# untitled.net
KiCad netlist of a schematic drawn in EAGLE
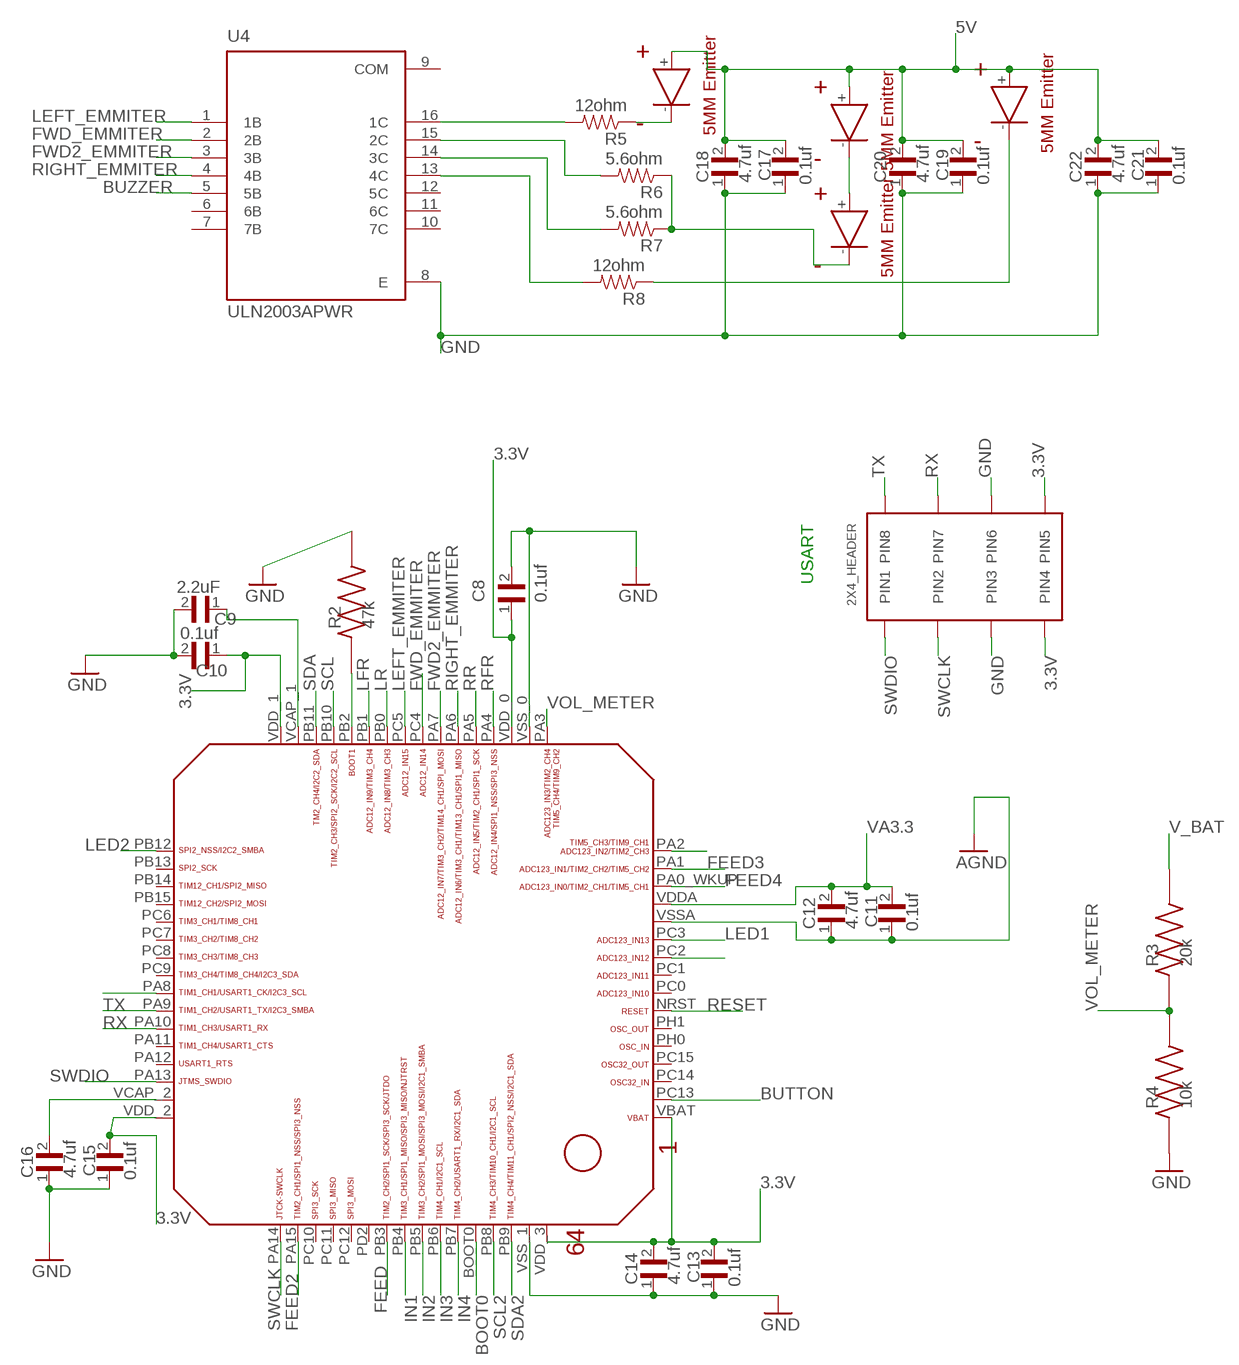
[diagram p0: schematic, sheet 1, part 1 of 2]
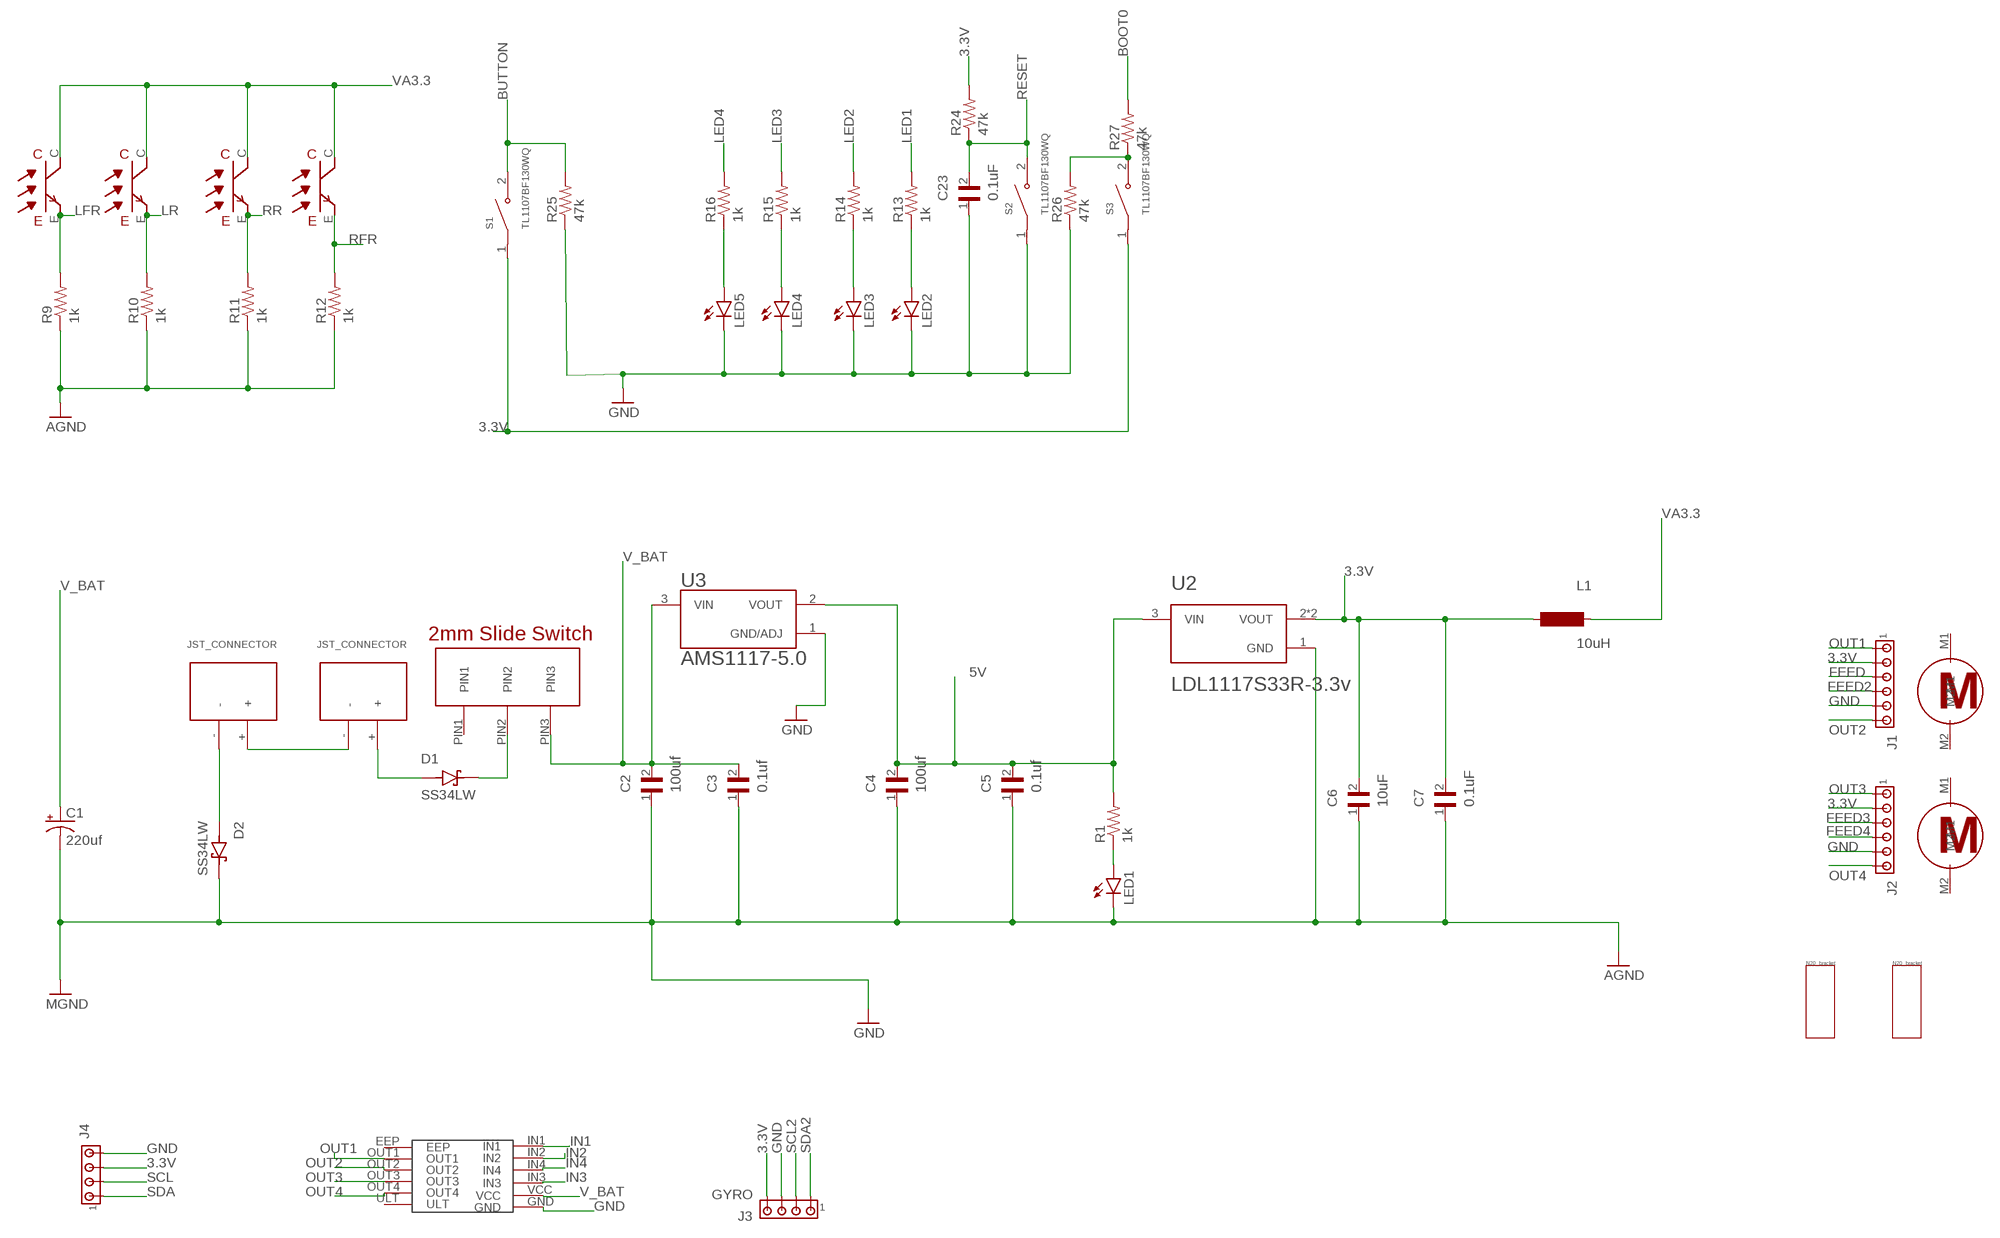
[diagram p1: schematic, sheet 1, part 2 of 2]

(export (version "E")
  (design (tool "Eeschema 10.0.6"))
  (components
    (comp (ref "C1")
      (value "220uf")
      (footprint "eagle-import:EIA3216")
      (libsource (lib "eagle-import") (part "CAP_POL1206"))
    )
    (comp (ref "C2")
      (value "100uf")
      (footprint "eagle-import:CAPC0603X35N")
      (fields (field (name "MF") "Murata") (field (name "MP") "GRM033R60J105MEA2D"))
      (libsource (lib "eagle-import") (part "GRM033R60J105MEA2D"))
    )
    (comp (ref "C3")
      (value "0.1uf")
      (footprint "eagle-import:CAPC0603X35N")
      (fields (field (name "MF") "Murata") (field (name "MP") "GRM033R60J105MEA2D"))
      (libsource (lib "eagle-import") (part "GRM033R60J105MEA2D"))
    )
    (comp (ref "C4")
      (value "100uf")
      (footprint "eagle-import:CAPC0603X35N")
      (fields (field (name "MF") "Murata") (field (name "MP") "GRM033R60J105MEA2D"))
      (libsource (lib "eagle-import") (part "GRM033R60J105MEA2D"))
    )
    (comp (ref "C5")
      (value "0.1uf")
      (footprint "eagle-import:CAPC0603X35N")
      (fields (field (name "MF") "Murata") (field (name "MP") "GRM033R60J105MEA2D"))
      (libsource (lib "eagle-import") (part "GRM033R60J105MEA2D"))
    )
    (comp (ref "C6")
      (value "10uF")
      (footprint "eagle-import:CAPC0603X35N")
      (fields (field (name "MF") "Murata") (field (name "MP") "GRM033R60J105MEA2D"))
      (libsource (lib "eagle-import") (part "GRM033R60J105MEA2D"))
    )
    (comp (ref "C7")
      (value "0.1uF")
      (footprint "eagle-import:CAPC0603X35N")
      (fields (field (name "MF") "Murata") (field (name "MP") "GRM033R60J105MEA2D"))
      (libsource (lib "eagle-import") (part "GRM033R60J105MEA2D"))
    )
    (comp (ref "C8")
      (value "0.1uf")
      (footprint "eagle-import:CAPC0603X35N")
      (fields (field (name "MF") "Murata") (field (name "MP") "GRM033R60J105MEA2D"))
      (libsource (lib "eagle-import") (part "GRM033R60J105MEA2D"))
    )
    (comp (ref "C9")
      (value "2.2uF")
      (footprint "eagle-import:CAPC0603X35N")
      (fields (field (name "MF") "Murata") (field (name "MP") "GRM033R60J105MEA2D"))
      (libsource (lib "eagle-import") (part "GRM033R60J105MEA2D"))
    )
    (comp (ref "C10")
      (value "0.1uf")
      (footprint "eagle-import:CAPC0603X35N")
      (fields (field (name "MF") "Murata") (field (name "MP") "GRM033R60J105MEA2D"))
      (libsource (lib "eagle-import") (part "GRM033R60J105MEA2D"))
    )
    (comp (ref "C11")
      (value "0.1uf")
      (footprint "eagle-import:CAPC0603X35N")
      (fields (field (name "MF") "Murata") (field (name "MP") "GRM033R60J105MEA2D"))
      (libsource (lib "eagle-import") (part "GRM033R60J105MEA2D"))
    )
    (comp (ref "C12")
      (value "4.7uf")
      (footprint "eagle-import:CAPC0603X35N")
      (fields (field (name "MF") "Murata") (field (name "MP") "GRM033R60J105MEA2D"))
      (libsource (lib "eagle-import") (part "GRM033R60J105MEA2D"))
    )
    (comp (ref "C13")
      (value "0.1uf")
      (footprint "eagle-import:CAPC0603X35N")
      (fields (field (name "MF") "Murata") (field (name "MP") "GRM033R60J105MEA2D"))
      (libsource (lib "eagle-import") (part "GRM033R60J105MEA2D"))
    )
    (comp (ref "C14")
      (value "4.7uf")
      (footprint "eagle-import:CAPC0603X35N")
      (fields (field (name "MF") "Murata") (field (name "MP") "GRM033R60J105MEA2D"))
      (libsource (lib "eagle-import") (part "GRM033R60J105MEA2D"))
    )
    (comp (ref "C15")
      (value "0.1uf")
      (footprint "eagle-import:CAPC0603X35N")
      (fields (field (name "MF") "Murata") (field (name "MP") "GRM033R60J105MEA2D"))
      (libsource (lib "eagle-import") (part "GRM033R60J105MEA2D"))
    )
    (comp (ref "C16")
      (value "4.7uf")
      (footprint "eagle-import:CAPC0603X35N")
      (fields (field (name "MF") "Murata") (field (name "MP") "GRM033R60J105MEA2D"))
      (libsource (lib "eagle-import") (part "GRM033R60J105MEA2D"))
    )
    (comp (ref "C17")
      (value "0.1uf")
      (footprint "eagle-import:CAPC0603X35N")
      (fields (field (name "MF") "Murata") (field (name "MP") "GRM033R60J105MEA2D"))
      (libsource (lib "eagle-import") (part "GRM033R60J105MEA2D"))
    )
    (comp (ref "C18")
      (value "4.7uf")
      (footprint "eagle-import:CAPC0603X35N")
      (fields (field (name "MF") "Murata") (field (name "MP") "GRM033R60J105MEA2D"))
      (libsource (lib "eagle-import") (part "GRM033R60J105MEA2D"))
    )
    (comp (ref "C19")
      (value "0.1uf")
      (footprint "eagle-import:CAPC0603X35N")
      (fields (field (name "MF") "Murata") (field (name "MP") "GRM033R60J105MEA2D"))
      (libsource (lib "eagle-import") (part "GRM033R60J105MEA2D"))
    )
    (comp (ref "C20")
      (value "4.7uf")
      (footprint "eagle-import:CAPC0603X35N")
      (fields (field (name "MF") "Murata") (field (name "MP") "GRM033R60J105MEA2D"))
      (libsource (lib "eagle-import") (part "GRM033R60J105MEA2D"))
    )
    (comp (ref "C21")
      (value "0.1uf")
      (footprint "eagle-import:CAPC0603X35N")
      (fields (field (name "MF") "Murata") (field (name "MP") "GRM033R60J105MEA2D"))
      (libsource (lib "eagle-import") (part "GRM033R60J105MEA2D"))
    )
    (comp (ref "C22")
      (value "4.7uf")
      (footprint "eagle-import:CAPC0603X35N")
      (fields (field (name "MF") "Murata") (field (name "MP") "GRM033R60J105MEA2D"))
      (libsource (lib "eagle-import") (part "GRM033R60J105MEA2D"))
    )
    (comp (ref "C23")
      (value "0.1uF")
      (footprint "eagle-import:CAPC0603X35N")
      (fields (field (name "MF") "Murata") (field (name "MP") "GRM033R60J105MEA2D"))
      (libsource (lib "eagle-import") (part "GRM033R60J105MEA2D"))
    )
    (comp (ref "D1")
      (value "SS34LW")
      (footprint "eagle-import:SODFL3718X102N")
      (fields (field (name "MF") "Taiwan Semiconductor"))
      (libsource (lib "eagle-import") (part "SS34LW"))
    )
    (comp (ref "D2")
      (value "SS34LW")
      (footprint "eagle-import:SODFL3718X102N")
      (fields (field (name "MF") "Taiwan Semiconductor"))
      (libsource (lib "eagle-import") (part "SS34LW"))
    )
    (comp (ref "EMMI1")
      (value "EMITTER")
      (footprint "eagle-import:EMITTER")
      (libsource (lib "eagle-import") (part "EMITTER"))
    )
    (comp (ref "J1")
      (value "MTA06-100")
      (footprint "eagle-import:10X06MTA")
      (libsource (lib "eagle-import") (part "MTA06-100"))
    )
    (comp (ref "J2")
      (value "MTA06-100")
      (footprint "eagle-import:10X06MTA")
      (libsource (lib "eagle-import") (part "MTA06-100"))
    )
    (comp (ref "J3")
      (value "GYRO")
      (footprint "eagle-import:10X04MTA")
      (libsource (lib "eagle-import") (part "MTA04-100"))
    )
    (comp (ref "J4")
      (value "MTA04-100")
      (footprint "eagle-import:10X04MTA")
      (libsource (lib "eagle-import") (part "MTA04-100"))
    )
    (comp (ref "L1")
      (value "10uH")
      (footprint "eagle-import:MS42")
      (libsource (lib "eagle-import") (part "MS42"))
    )
    (comp (ref "LED1")
      (value "LEDCHIPLED_0805")
      (footprint "eagle-import:CHIPLED_0805")
      (libsource (lib "eagle-import") (part "LEDCHIPLED_0805"))
    )
    (comp (ref "LED2")
      (value "LEDCHIPLED_0805")
      (footprint "eagle-import:CHIPLED_0805")
      (libsource (lib "eagle-import") (part "LEDCHIPLED_0805"))
    )
    (comp (ref "LED3")
      (value "LEDCHIPLED_0805")
      (footprint "eagle-import:CHIPLED_0805")
      (libsource (lib "eagle-import") (part "LEDCHIPLED_0805"))
    )
    (comp (ref "LED4")
      (value "LEDCHIPLED_0805")
      (footprint "eagle-import:CHIPLED_0805")
      (libsource (lib "eagle-import") (part "LEDCHIPLED_0805"))
    )
    (comp (ref "LED5")
      (value "LEDCHIPLED_0805")
      (footprint "eagle-import:CHIPLED_0805")
      (libsource (lib "eagle-import") (part "LEDCHIPLED_0805"))
    )
    (comp (ref "R1")
      (value "1k")
      (footprint "eagle-import:0603-RES")
      (libsource (lib "eagle-import") (part "RESISTOR0603-RES"))
    )
    (comp (ref "R2")
      (value "47k")
      (footprint "eagle-import:RES_ERJU01F3570C")
      (fields (field (name "MF") "Panasonic") (field (name "MP") "ERJ-U01F3570C"))
      (libsource (lib "eagle-import") (part "ERJU01F3570C"))
    )
    (comp (ref "R3")
      (value "20k")
      (footprint "eagle-import:RES_ERJU01F3570C")
      (fields (field (name "MF") "Panasonic") (field (name "MP") "ERJ-U01F3570C"))
      (libsource (lib "eagle-import") (part "ERJU01F3570C"))
    )
    (comp (ref "R4")
      (value "10k")
      (footprint "eagle-import:RES_ERJU01F3570C")
      (fields (field (name "MF") "Panasonic") (field (name "MP") "ERJ-U01F3570C"))
      (libsource (lib "eagle-import") (part "ERJU01F3570C"))
    )
    (comp (ref "R5")
      (value "12ohm")
      (footprint "eagle-import:0603-RES")
      (libsource (lib "eagle-import") (part "RESISTOR0603-RES"))
    )
    (comp (ref "R6")
      (value "5.6ohm")
      (footprint "eagle-import:0603-RES")
      (libsource (lib "eagle-import") (part "RESISTOR0603-RES"))
    )
    (comp (ref "R7")
      (value "5.6ohm")
      (footprint "eagle-import:0603-RES")
      (libsource (lib "eagle-import") (part "RESISTOR0603-RES"))
    )
    (comp (ref "R8")
      (value "12ohm")
      (footprint "eagle-import:0603-RES")
      (libsource (lib "eagle-import") (part "RESISTOR0603-RES"))
    )
    (comp (ref "R9")
      (value "1k")
      (footprint "eagle-import:0603-RES")
      (libsource (lib "eagle-import") (part "RESISTOR0603-RES"))
    )
    (comp (ref "R10")
      (value "1k")
      (footprint "eagle-import:0603-RES")
      (libsource (lib "eagle-import") (part "RESISTOR0603-RES"))
    )
    (comp (ref "R11")
      (value "1k")
      (footprint "eagle-import:0603-RES")
      (libsource (lib "eagle-import") (part "RESISTOR0603-RES"))
    )
    (comp (ref "R12")
      (value "1k")
      (footprint "eagle-import:0603-RES")
      (libsource (lib "eagle-import") (part "RESISTOR0603-RES"))
    )
    (comp (ref "R13")
      (value "1k")
      (footprint "eagle-import:0603-RES")
      (libsource (lib "eagle-import") (part "RESISTOR0603-RES"))
    )
    (comp (ref "R14")
      (value "1k")
      (footprint "eagle-import:0603-RES")
      (libsource (lib "eagle-import") (part "RESISTOR0603-RES"))
    )
    (comp (ref "R15")
      (value "1k")
      (footprint "eagle-import:0603-RES")
      (libsource (lib "eagle-import") (part "RESISTOR0603-RES"))
    )
    (comp (ref "R16")
      (value "1k")
      (footprint "eagle-import:0603-RES")
      (libsource (lib "eagle-import") (part "RESISTOR0603-RES"))
    )
    (comp (ref "R24")
      (value "47k")
      (footprint "eagle-import:0603-RES")
      (libsource (lib "eagle-import") (part "RESISTOR0603-RES"))
    )
    (comp (ref "R25")
      (value "47k")
      (footprint "eagle-import:0603-RES")
      (libsource (lib "eagle-import") (part "RESISTOR0603-RES"))
    )
    (comp (ref "R26")
      (value "47k")
      (footprint "eagle-import:0603-RES")
      (libsource (lib "eagle-import") (part "RESISTOR0603-RES"))
    )
    (comp (ref "R27")
      (value "47k")
      (footprint "eagle-import:0603-RES")
      (libsource (lib "eagle-import") (part "RESISTOR0603-RES"))
    )
    (comp (ref "S1")
      (value "TL1107BF130WQ")
      (footprint "eagle-import:SW_TL1107BF130WQ")
      (fields (field (name "MF") "E-Switch"))
      (libsource (lib "eagle-import") (part "TL1107BF130WQ"))
    )
    (comp (ref "S2")
      (value "TL1107BF130WQ")
      (footprint "eagle-import:SW_TL1107BF130WQ")
      (fields (field (name "MF") "E-Switch"))
      (libsource (lib "eagle-import") (part "TL1107BF130WQ"))
    )
    (comp (ref "S3")
      (value "TL1107BF130WQ")
      (footprint "eagle-import:SW_TL1107BF130WQ")
      (fields (field (name "MF") "E-Switch"))
      (libsource (lib "eagle-import") (part "TL1107BF130WQ"))
    )
    (comp (ref "STM32F405RGT6")
      (value "STM32F405/415_LQFP64")
      (footprint "eagle-import:STM32F405_415_LQFP64")
      (libsource (lib "eagle-import") (part "STM32F405/415_LQFP64"))
    )
    (comp (ref "U$1")
      (value "N20_BRACKET")
      (footprint "eagle-import:BRACKER")
      (libsource (lib "eagle-import") (part "N20_BRACKET"))
    )
    (comp (ref "U$2")
      (value "MOTOR_N20")
      (footprint "eagle-import:MOTOR_N20")
      (libsource (lib "eagle-import") (part "MOTOR_N20"))
    )
    (comp (ref "U$3")
      (value "MOTOR_N20")
      (footprint "eagle-import:MOTOR_N20")
      (libsource (lib "eagle-import") (part "MOTOR_N20"))
    )
    (comp (ref "U$4")
      (value "N20_BRACKET")
      (footprint "eagle-import:BRACKER")
      (libsource (lib "eagle-import") (part "N20_BRACKET"))
    )
    (comp (ref "U$5")
      (value "JST_CONNECTOR_FEMALE")
      (footprint "eagle-import:JST_CONNECTOR_FEMALE")
      (libsource (lib "eagle-import") (part "JST_CONNECTOR_FEMALE"))
    )
    (comp (ref "U$6")
      (value "JST_CONNECTOR_FEMALE")
      (footprint "eagle-import:JST_CONNECTOR_FEMALE")
      (libsource (lib "eagle-import") (part "JST_CONNECTOR_FEMALE"))
    )
    (comp (ref "U$8")
      (value "2MMS_SLIDE_SWITCH")
      (footprint "eagle-import:2MMS_SLIDE_SWITCH")
      (libsource (lib "eagle-import") (part "2MMS_SLIDE_SWITCH"))
    )
    (comp (ref "U$10")
      (value "2X3_HEADER")
      (footprint "eagle-import:2X3_HEADER")
      (libsource (lib "eagle-import") (part "2X3_HEADER"))
    )
    (comp (ref "U$11")
      (value "DRV8833")
      (footprint "eagle-import:DRV8833")
      (libsource (lib "eagle-import") (part "DRV8833"))
    )
    (comp (ref "U$12")
      (value "RECEIVER")
      (footprint "eagle-import:RECEIVER")
      (libsource (lib "eagle-import") (part "RECEIVER"))
    )
    (comp (ref "U$13")
      (value "EMITTER")
      (footprint "eagle-import:EMITTER")
      (libsource (lib "eagle-import") (part "EMITTER"))
    )
    (comp (ref "U$14")
      (value "EMITTER")
      (footprint "eagle-import:EMITTER")
      (libsource (lib "eagle-import") (part "EMITTER"))
    )
    (comp (ref "U$15")
      (value "EMITTER")
      (footprint "eagle-import:EMITTER")
      (libsource (lib "eagle-import") (part "EMITTER"))
    )
    (comp (ref "U$16")
      (value "RECEIVER")
      (footprint "eagle-import:RECEIVER")
      (libsource (lib "eagle-import") (part "RECEIVER"))
    )
    (comp (ref "U$17")
      (value "RECEIVER")
      (footprint "eagle-import:RECEIVER")
      (libsource (lib "eagle-import") (part "RECEIVER"))
    )
    (comp (ref "U$18")
      (value "RECEIVER")
      (footprint "eagle-import:RECEIVER")
      (libsource (lib "eagle-import") (part "RECEIVER"))
    )
    (comp (ref "U2")
      (value "LDL1117S33R-3.3v")
      (footprint "eagle-import:SOT230P700X180-4N")
      (fields (field (name "MF") "STMicroelectronics") (field (name "MP") "LDL1117S33R"))
      (libsource (lib "eagle-import") (part "LDL1117S33R"))
    )
    (comp (ref "U3")
      (value "AMS1117-5.0")
      (footprint "eagle-import:SOT229P700X180-4N")
      (fields (field (name "MF") "Advanced Monolithic Systems"))
      (libsource (lib "eagle-import") (part "AMS1117-5.0"))
    )
    (comp (ref "U4")
      (value "ULN2003APWR")
      (footprint "eagle-import:SOP65P640X120-16N")
      (fields (field (name "MF") "Texas Instruments"))
      (libsource (lib "eagle-import") (part "ULN2003APWR"))
    )
  )
  (nets
    (net (code "1") (name "/3.3V") (class "Default")
      (node (ref "C10") (pin "1") (pinfunction "1_1") (pintype "passive"))
      (node (ref "C13") (pin "2") (pinfunction "2_2") (pintype "passive"))
      (node (ref "C14") (pin "2") (pinfunction "2_2") (pintype "passive"))
      (node (ref "C15") (pin "2") (pinfunction "2_2") (pintype "passive"))
      (node (ref "C6") (pin "2") (pinfunction "2_2") (pintype "passive"))
      (node (ref "C7") (pin "2") (pinfunction "2_2") (pintype "passive"))
      (node (ref "C8") (pin "1") (pinfunction "1_1") (pintype "passive"))
      (node (ref "J1") (pin "2") (pinfunction "2_2") (pintype "passive"))
      (node (ref "J2") (pin "2") (pinfunction "2_2") (pintype "passive"))
      (node (ref "J3") (pin "4") (pinfunction "4_4") (pintype "passive"))
      (node (ref "J4") (pin "3") (pinfunction "3_3") (pintype "passive"))
      (node (ref "L1") (pin "1") (pinfunction "1_1") (pintype "passive"))
      (node (ref "R24") (pin "2") (pinfunction "2_2") (pintype "passive"))
      (node (ref "S1") (pin "1") (pinfunction "1_1") (pintype "passive"))
      (node (ref "S3") (pin "1") (pinfunction "1_1") (pintype "passive"))
      (node (ref "STM32F405RGT6") (pin "VBAT") (pinfunction "VBAT_VBAT") (pintype "bidirectional"))
      (node (ref "STM32F405RGT6") (pin "VDD_0") (pinfunction "VDD_0_VDD_0") (pintype "bidirectional"))
      (node (ref "STM32F405RGT6") (pin "VDD_1") (pinfunction "VDD_1_VDD_1") (pintype "bidirectional"))
      (node (ref "STM32F405RGT6") (pin "VDD_2") (pinfunction "VDD_2_VDD_2") (pintype "bidirectional"))
      (node (ref "STM32F405RGT6") (pin "VDD_3") (pinfunction "VDD_3_VDD_3") (pintype "bidirectional"))
      (node (ref "U$10") (pin "PIN4") (pinfunction "PIN4_PIN4") (pintype "bidirectional"))
      (node (ref "U$10") (pin "PIN5") (pinfunction "PIN5_PIN5") (pintype "bidirectional"))
      (node (ref "U2") (pin "2") (pinfunction "VOUT_2") (pintype "output"))
      (node (ref "U2") (pin "4") (pinfunction "VOUT_4") (pintype "output"))
    )
    (net (code "2") (name "/5V") (class "Default")
      (node (ref "C17") (pin "2") (pinfunction "2_2") (pintype "passive"))
      (node (ref "C18") (pin "2") (pinfunction "2_2") (pintype "passive"))
      (node (ref "C19") (pin "2") (pinfunction "2_2") (pintype "passive"))
      (node (ref "C20") (pin "2") (pinfunction "2_2") (pintype "passive"))
      (node (ref "C21") (pin "2") (pinfunction "2_2") (pintype "passive"))
      (node (ref "C22") (pin "2") (pinfunction "2_2") (pintype "passive"))
      (node (ref "C4") (pin "2") (pinfunction "2_2") (pintype "passive"))
      (node (ref "C5") (pin "2") (pinfunction "2_2") (pintype "passive"))
      (node (ref "EMMI1") (pin "+") (pinfunction "+_+") (pintype "bidirectional"))
      (node (ref "R1") (pin "2") (pinfunction "2_2") (pintype "passive"))
      (node (ref "U$13") (pin "+") (pinfunction "+_+") (pintype "bidirectional"))
      (node (ref "U$15") (pin "+") (pinfunction "+_+") (pintype "bidirectional"))
      (node (ref "U2") (pin "3") (pinfunction "VIN_3") (pintype "input"))
      (node (ref "U3") (pin "2") (pinfunction "VOUT_2") (pintype "output"))
    )
    (net (code "3") (name "/BOOT0") (class "Default")
      (node (ref "R27") (pin "2") (pinfunction "2_2") (pintype "passive"))
      (node (ref "STM32F405RGT6") (pin "BOOT0") (pinfunction "BOOT0_BOOT0") (pintype "bidirectional"))
    )
    (net (code "4") (name "/BUTTON") (class "Default")
      (node (ref "R25") (pin "2") (pinfunction "2_2") (pintype "passive"))
      (node (ref "S1") (pin "2") (pinfunction "2_2") (pintype "passive"))
      (node (ref "STM32F405RGT6") (pin "PC13") (pinfunction "PC13_PC13") (pintype "bidirectional"))
    )
    (net (code "5") (name "/BUZZER") (class "Default")
      (node (ref "U4") (pin "5") (pinfunction "5B_5") (pintype "input"))
    )
    (net (code "6") (name "/COM") (class "Default")
      (node (ref "U4") (pin "9") (pinfunction "COM_9") (pintype "power_in"))
    )
    (net (code "7") (name "/FEED") (class "Default")
      (node (ref "J1") (pin "3") (pinfunction "3_3") (pintype "passive"))
      (node (ref "STM32F405RGT6") (pin "PB3") (pinfunction "PB3_PB3") (pintype "bidirectional"))
    )
    (net (code "8") (name "/FEED2") (class "Default")
      (node (ref "J1") (pin "4") (pinfunction "4_4") (pintype "passive"))
      (node (ref "STM32F405RGT6") (pin "PA15") (pinfunction "PA15_PA15") (pintype "bidirectional"))
    )
    (net (code "9") (name "/FEED3") (class "Default")
      (node (ref "J2") (pin "3") (pinfunction "3_3") (pintype "passive"))
      (node (ref "STM32F405RGT6") (pin "PA1") (pinfunction "PA1_PA1") (pintype "bidirectional"))
    )
    (net (code "10") (name "/FEED4") (class "Default")
      (node (ref "J2") (pin "4") (pinfunction "4_4") (pintype "passive"))
      (node (ref "STM32F405RGT6") (pin "PA0_WKUP") (pinfunction "PA0_AKUP_PA0_WKUP") (pintype "bidirectional"))
    )
    (net (code "11") (name "/FWD2_EMMITER") (class "Default")
      (node (ref "STM32F405RGT6") (pin "PA7") (pinfunction "PA7_PA7") (pintype "bidirectional"))
      (node (ref "U4") (pin "3") (pinfunction "3B_3") (pintype "input"))
    )
    (net (code "12") (name "/FWD_EMMITER") (class "Default")
      (node (ref "STM32F405RGT6") (pin "PC4") (pinfunction "PC4_PC4") (pintype "bidirectional"))
      (node (ref "U4") (pin "2") (pinfunction "2B_2") (pintype "input"))
    )
    (net (code "13") (name "/IN1") (class "Default")
      (node (ref "STM32F405RGT6") (pin "PB4") (pinfunction "PB4_PB4") (pintype "bidirectional"))
      (node (ref "U$11") (pin "IN1") (pinfunction "IN1_IN1") (pintype "bidirectional"))
    )
    (net (code "14") (name "/IN2") (class "Default")
      (node (ref "STM32F405RGT6") (pin "PB5") (pinfunction "PB5_PB5") (pintype "bidirectional"))
      (node (ref "U$11") (pin "IN2") (pinfunction "IN2_IN2") (pintype "bidirectional"))
    )
    (net (code "15") (name "/IN3") (class "Default")
      (node (ref "STM32F405RGT6") (pin "PB6") (pinfunction "PB6_PB6") (pintype "bidirectional"))
      (node (ref "U$11") (pin "IN3") (pinfunction "IN3_IN3") (pintype "bidirectional"))
    )
    (net (code "16") (name "/IN4") (class "Default")
      (node (ref "STM32F405RGT6") (pin "PB7") (pinfunction "PB7_PB7") (pintype "bidirectional"))
      (node (ref "U$11") (pin "IN4") (pinfunction "IN4_IN4") (pintype "bidirectional"))
    )
    (net (code "17") (name "/LED1") (class "Default")
      (node (ref "R13") (pin "2") (pinfunction "2_2") (pintype "passive"))
      (node (ref "STM32F405RGT6") (pin "PC3") (pinfunction "PC3_PC3") (pintype "bidirectional"))
    )
    (net (code "18") (name "/LED2") (class "Default")
      (node (ref "R14") (pin "2") (pinfunction "2_2") (pintype "passive"))
      (node (ref "STM32F405RGT6") (pin "PB12") (pinfunction "PB12_PB12") (pintype "bidirectional"))
    )
    (net (code "19") (name "/LED3") (class "Default")
      (node (ref "R15") (pin "2") (pinfunction "2_2") (pintype "passive"))
      (node (ref "STM32F405RGT6") (pin "PC2") (pinfunction "PC2_PC2") (pintype "bidirectional"))
    )
    (net (code "20") (name "/LED4") (class "Default")
      (node (ref "R16") (pin "2") (pinfunction "2_2") (pintype "passive"))
      (node (ref "STM32F405RGT6") (pin "PA8") (pinfunction "PA8_PA8") (pintype "bidirectional"))
    )
    (net (code "21") (name "/LEFT_EMMITER") (class "Default")
      (node (ref "STM32F405RGT6") (pin "PC5") (pinfunction "PC5_PC5") (pintype "bidirectional"))
      (node (ref "U4") (pin "1") (pinfunction "1B_1") (pintype "input"))
    )
    (net (code "22") (name "/LFR") (class "Default")
      (node (ref "R9") (pin "2") (pinfunction "2_2") (pintype "passive"))
      (node (ref "STM32F405RGT6") (pin "PB1") (pinfunction "PB1_PB1") (pintype "bidirectional"))
      (node (ref "U$18") (pin "E") (pinfunction "E_E") (pintype "bidirectional"))
    )
    (net (code "23") (name "/LR") (class "Default")
      (node (ref "R10") (pin "2") (pinfunction "2_2") (pintype "passive"))
      (node (ref "STM32F405RGT6") (pin "PB0") (pinfunction "PB0_PB0") (pintype "bidirectional"))
      (node (ref "U$17") (pin "E") (pinfunction "E_E") (pintype "bidirectional"))
    )
    (net (code "24") (name "/OUT1") (class "Default")
      (node (ref "J1") (pin "1") (pinfunction "1_1") (pintype "passive"))
      (node (ref "U$11") (pin "OUT1") (pinfunction "OUT1_OUT1") (pintype "bidirectional"))
    )
    (net (code "25") (name "/OUT2") (class "Default")
      (node (ref "J1") (pin "6") (pinfunction "6_6") (pintype "passive"))
      (node (ref "U$11") (pin "OUT2") (pinfunction "OUT2_OUT2") (pintype "bidirectional"))
    )
    (net (code "26") (name "/OUT3") (class "Default")
      (node (ref "J2") (pin "1") (pinfunction "1_1") (pintype "passive"))
      (node (ref "U$11") (pin "OUT3") (pinfunction "OUT3_OUT3") (pintype "bidirectional"))
    )
    (net (code "27") (name "/OUT4") (class "Default")
      (node (ref "J2") (pin "6") (pinfunction "6_6") (pintype "passive"))
      (node (ref "U$11") (pin "OUT4") (pinfunction "OUT4_OUT4") (pintype "bidirectional"))
    )
    (net (code "28") (name "/RESET") (class "Default")
      (node (ref "C23") (pin "2") (pinfunction "2_2") (pintype "passive"))
      (node (ref "R24") (pin "1") (pinfunction "1_1") (pintype "passive"))
      (node (ref "S2") (pin "2") (pinfunction "2_2") (pintype "passive"))
      (node (ref "STM32F405RGT6") (pin "NRST") (pinfunction "NRST_NRST") (pintype "bidirectional"))
    )
    (net (code "29") (name "/RFR") (class "Default")
      (node (ref "R12") (pin "2") (pinfunction "2_2") (pintype "passive"))
      (node (ref "STM32F405RGT6") (pin "PA4") (pinfunction "PA4_PA4") (pintype "bidirectional"))
      (node (ref "U$12") (pin "E") (pinfunction "E_E") (pintype "bidirectional"))
    )
    (net (code "30") (name "/RIGHT_EMMITER") (class "Default")
      (node (ref "STM32F405RGT6") (pin "PA6") (pinfunction "PA6_PA6") (pintype "bidirectional"))
      (node (ref "U4") (pin "4") (pinfunction "4B_4") (pintype "input"))
    )
    (net (code "31") (name "/RR") (class "Default")
      (node (ref "R11") (pin "2") (pinfunction "2_2") (pintype "passive"))
      (node (ref "STM32F405RGT6") (pin "PA5") (pinfunction "PA5_PA5") (pintype "bidirectional"))
      (node (ref "U$16") (pin "E") (pinfunction "E_E") (pintype "bidirectional"))
    )
    (net (code "32") (name "/RX") (class "Default")
      (node (ref "STM32F405RGT6") (pin "PA10") (pinfunction "PA10_PA10") (pintype "bidirectional"))
      (node (ref "U$10") (pin "PIN7") (pinfunction "PIN7_PIN7") (pintype "bidirectional"))
    )
    (net (code "33") (name "/SCL") (class "Default")
      (node (ref "J4") (pin "2") (pinfunction "2_2") (pintype "passive"))
      (node (ref "STM32F405RGT6") (pin "PB10") (pinfunction "PB10_PB10") (pintype "bidirectional"))
    )
    (net (code "34") (name "/SCL2") (class "Default")
      (node (ref "J3") (pin "2") (pinfunction "2_2") (pintype "passive"))
      (node (ref "STM32F405RGT6") (pin "PB8") (pinfunction "PB8_PB8") (pintype "bidirectional"))
    )
    (net (code "35") (name "/SDA") (class "Default")
      (node (ref "J4") (pin "1") (pinfunction "1_1") (pintype "passive"))
      (node (ref "STM32F405RGT6") (pin "PB11") (pinfunction "PB11_PB11") (pintype "bidirectional"))
    )
    (net (code "36") (name "/SDA2") (class "Default")
      (node (ref "J3") (pin "1") (pinfunction "1_1") (pintype "passive"))
      (node (ref "STM32F405RGT6") (pin "PB9") (pinfunction "PB9_PB9") (pintype "bidirectional"))
    )
    (net (code "37") (name "/SWCLK") (class "Default")
      (node (ref "STM32F405RGT6") (pin "PA14") (pinfunction "PA14_PA14") (pintype "bidirectional"))
      (node (ref "U$10") (pin "PIN2") (pinfunction "PIN2_PIN2") (pintype "bidirectional"))
    )
    (net (code "38") (name "/SWDIO") (class "Default")
      (node (ref "STM32F405RGT6") (pin "PA13") (pinfunction "PA13_PA13") (pintype "bidirectional"))
      (node (ref "U$10") (pin "PIN1") (pinfunction "PIN1_PIN1") (pintype "bidirectional"))
    )
    (net (code "39") (name "/TX") (class "Default")
      (node (ref "STM32F405RGT6") (pin "PA9") (pinfunction "PA9_PA9") (pintype "bidirectional"))
      (node (ref "U$10") (pin "PIN8") (pinfunction "PIN8_PIN8") (pintype "bidirectional"))
    )
    (net (code "40") (name "/VA3.3") (class "Default")
      (node (ref "C11") (pin "2") (pinfunction "2_2") (pintype "passive"))
      (node (ref "C12") (pin "2") (pinfunction "2_2") (pintype "passive"))
      (node (ref "L1") (pin "2") (pinfunction "2_2") (pintype "passive"))
      (node (ref "STM32F405RGT6") (pin "VDDA") (pinfunction "VDDA_VDDA") (pintype "bidirectional"))
      (node (ref "U$12") (pin "C") (pinfunction "C_C") (pintype "bidirectional"))
      (node (ref "U$16") (pin "C") (pinfunction "C_C") (pintype "bidirectional"))
      (node (ref "U$17") (pin "C") (pinfunction "C_C") (pintype "bidirectional"))
      (node (ref "U$18") (pin "C") (pinfunction "C_C") (pintype "bidirectional"))
    )
    (net (code "41") (name "/VOL_METER") (class "Default")
      (node (ref "R3") (pin "1") (pinfunction "1_1") (pintype "passive"))
      (node (ref "R4") (pin "2") (pinfunction "2_2") (pintype "passive"))
      (node (ref "STM32F405RGT6") (pin "PA3") (pinfunction "PA3_PA3") (pintype "bidirectional"))
    )
    (net (code "42") (name "/V_BAT") (class "Default")
      (node (ref "C1") (pin "A") (pinfunction "+_A") (pintype "passive"))
      (node (ref "C2") (pin "2") (pinfunction "2_2") (pintype "passive"))
      (node (ref "C3") (pin "2") (pinfunction "2_2") (pintype "passive"))
      (node (ref "R3") (pin "2") (pinfunction "2_2") (pintype "passive"))
      (node (ref "U$11") (pin "VCC") (pinfunction "VCC_VCC") (pintype "bidirectional"))
      (node (ref "U$8") (pin "PIN3") (pinfunction "PIN3_PIN3") (pintype "bidirectional"))
      (node (ref "U3") (pin "3") (pinfunction "VIN_3") (pintype "input"))
    )
    (net (code "43") (name "AGND") (class "Default")
      (node (ref "C1") (pin "C") (pinfunction "-_C") (pintype "passive"))
      (node (ref "C10") (pin "2") (pinfunction "2_2") (pintype "passive"))
      (node (ref "C11") (pin "1") (pinfunction "1_1") (pintype "passive"))
      (node (ref "C12") (pin "1") (pinfunction "1_1") (pintype "passive"))
      (node (ref "C13") (pin "1") (pinfunction "1_1") (pintype "passive"))
      (node (ref "C14") (pin "1") (pinfunction "1_1") (pintype "passive"))
      (node (ref "C15") (pin "1") (pinfunction "1_1") (pintype "passive"))
      (node (ref "C16") (pin "1") (pinfunction "1_1") (pintype "passive"))
      (node (ref "C17") (pin "1") (pinfunction "1_1") (pintype "passive"))
      (node (ref "C18") (pin "1") (pinfunction "1_1") (pintype "passive"))
      (node (ref "C19") (pin "1") (pinfunction "1_1") (pintype "passive"))
      (node (ref "C2") (pin "1") (pinfunction "1_1") (pintype "passive"))
      (node (ref "C20") (pin "1") (pinfunction "1_1") (pintype "passive"))
      (node (ref "C21") (pin "1") (pinfunction "1_1") (pintype "passive"))
      (node (ref "C22") (pin "1") (pinfunction "1_1") (pintype "passive"))
      (node (ref "C23") (pin "1") (pinfunction "1_1") (pintype "passive"))
      (node (ref "C3") (pin "1") (pinfunction "1_1") (pintype "passive"))
      (node (ref "C4") (pin "1") (pinfunction "1_1") (pintype "passive"))
      (node (ref "C5") (pin "1") (pinfunction "1_1") (pintype "passive"))
      (node (ref "C6") (pin "1") (pinfunction "1_1") (pintype "passive"))
      (node (ref "C7") (pin "1") (pinfunction "1_1") (pintype "passive"))
      (node (ref "C8") (pin "2") (pinfunction "2_2") (pintype "passive"))
      (node (ref "C9") (pin "2") (pinfunction "2_2") (pintype "passive"))
      (node (ref "D2") (pin "C") (pinfunction "K_C") (pintype "passive"))
      (node (ref "J1") (pin "5") (pinfunction "5_5") (pintype "passive"))
      (node (ref "J2") (pin "5") (pinfunction "5_5") (pintype "passive"))
      (node (ref "J3") (pin "3") (pinfunction "3_3") (pintype "passive"))
      (node (ref "J4") (pin "4") (pinfunction "4_4") (pintype "passive"))
      (node (ref "LED1") (pin "C") (pinfunction "C_C") (pintype "passive"))
      (node (ref "LED2") (pin "C") (pinfunction "C_C") (pintype "passive"))
      (node (ref "LED3") (pin "C") (pinfunction "C_C") (pintype "passive"))
      (node (ref "LED4") (pin "C") (pinfunction "C_C") (pintype "passive"))
      (node (ref "LED5") (pin "C") (pinfunction "C_C") (pintype "passive"))
      (node (ref "R10") (pin "1") (pinfunction "1_1") (pintype "passive"))
      (node (ref "R11") (pin "1") (pinfunction "1_1") (pintype "passive"))
      (node (ref "R12") (pin "1") (pinfunction "1_1") (pintype "passive"))
      (node (ref "R2") (pin "2") (pinfunction "2_2") (pintype "passive"))
      (node (ref "R25") (pin "1") (pinfunction "1_1") (pintype "passive"))
      (node (ref "R26") (pin "1") (pinfunction "1_1") (pintype "passive"))
      (node (ref "R4") (pin "1") (pinfunction "1_1") (pintype "passive"))
      (node (ref "R9") (pin "1") (pinfunction "1_1") (pintype "passive"))
      (node (ref "S2") (pin "1") (pinfunction "1_1") (pintype "passive"))
      (node (ref "STM32F405RGT6") (pin "VSSA") (pinfunction "VSSA_VSSA") (pintype "bidirectional"))
      (node (ref "STM32F405RGT6") (pin "VSS_0") (pinfunction "VSS_0_VSS_0") (pintype "bidirectional"))
      (node (ref "STM32F405RGT6") (pin "VSS_1") (pinfunction "VSS_1_VSS_1") (pintype "bidirectional"))
      (node (ref "U$10") (pin "PIN3") (pinfunction "PIN3_PIN3") (pintype "bidirectional"))
      (node (ref "U$10") (pin "PIN6") (pinfunction "PIN6_PIN6") (pintype "bidirectional"))
      (node (ref "U$11") (pin "GND") (pinfunction "GND_GND") (pintype "bidirectional"))
      (node (ref "U2") (pin "1") (pinfunction "GND_1") (pintype "power_in"))
      (node (ref "U3") (pin "1") (pinfunction "GND/ADJ_1") (pintype "power_in"))
      (node (ref "U4") (pin "8") (pinfunction "E_8") (pintype "power_in"))
    )
    (net (code "44") (name "Net-(C9-Pad1)") (class "Default")
      (node (ref "C9") (pin "1") (pinfunction "1_1") (pintype "passive"))
      (node (ref "STM32F405RGT6") (pin "VCAP_1") (pinfunction "VCAP_1_VCAP_1") (pintype "bidirectional"))
    )
    (net (code "45") (name "Net-(C16-Pad2)") (class "Default")
      (node (ref "C16") (pin "2") (pinfunction "2_2") (pintype "passive"))
      (node (ref "STM32F405RGT6") (pin "VCAP_2") (pinfunction "VCAP_2_VCAP_2") (pintype "bidirectional"))
    )
    (net (code "46") (name "Net-(D1-K)") (class "Default")
      (node (ref "D1") (pin "C") (pinfunction "K_C") (pintype "passive"))
      (node (ref "U$8") (pin "PIN2") (pinfunction "PIN2_PIN2") (pintype "bidirectional"))
    )
    (net (code "47") (name "Net-(D1-PadA)") (class "Default")
      (node (ref "D1") (pin "A") (pinfunction "A_A") (pintype "passive"))
      (node (ref "U$6") (pin "+") (pinfunction "+_+") (pintype "bidirectional"))
    )
    (net (code "48") (name "Net-(D2-PadA)") (class "Default")
      (node (ref "D2") (pin "A") (pinfunction "A_A") (pintype "passive"))
      (node (ref "U$5") (pin "-") (pinfunction "-_-") (pintype "bidirectional"))
    )
    (net (code "49") (name "Net-(EMMI1-Pad-)") (class "Default")
      (node (ref "EMMI1") (pin "-") (pinfunction "-_-") (pintype "bidirectional"))
      (node (ref "R5") (pin "1") (pinfunction "1_1") (pintype "passive"))
    )
    (net (code "50") (name "Net-(LED1-PadA)") (class "Default")
      (node (ref "LED1") (pin "A") (pinfunction "A_A") (pintype "passive"))
      (node (ref "R1") (pin "1") (pinfunction "1_1") (pintype "passive"))
    )
    (net (code "51") (name "Net-(LED2-PadA)") (class "Default")
      (node (ref "LED2") (pin "A") (pinfunction "A_A") (pintype "passive"))
      (node (ref "R13") (pin "1") (pinfunction "1_1") (pintype "passive"))
    )
    (net (code "52") (name "Net-(LED3-PadA)") (class "Default")
      (node (ref "LED3") (pin "A") (pinfunction "A_A") (pintype "passive"))
      (node (ref "R14") (pin "1") (pinfunction "1_1") (pintype "passive"))
    )
    (net (code "53") (name "Net-(LED4-PadA)") (class "Default")
      (node (ref "LED4") (pin "A") (pinfunction "A_A") (pintype "passive"))
      (node (ref "R15") (pin "1") (pinfunction "1_1") (pintype "passive"))
    )
    (net (code "54") (name "Net-(LED5-PadA)") (class "Default")
      (node (ref "LED5") (pin "A") (pinfunction "A_A") (pintype "passive"))
      (node (ref "R16") (pin "1") (pinfunction "1_1") (pintype "passive"))
    )
    (net (code "55") (name "Net-(R2-Pad1)") (class "Default")
      (node (ref "R2") (pin "1") (pinfunction "1_1") (pintype "passive"))
      (node (ref "STM32F405RGT6") (pin "PB2") (pinfunction "PB2_PB2") (pintype "bidirectional"))
    )
    (net (code "56") (name "Net-(R6-Pad1)") (class "Default")
      (node (ref "R6") (pin "1") (pinfunction "1_1") (pintype "passive"))
      (node (ref "R7") (pin "1") (pinfunction "1_1") (pintype "passive"))
      (node (ref "U$14") (pin "-") (pinfunction "-_-") (pintype "bidirectional"))
    )
    (net (code "57") (name "Net-(R8-Pad1)") (class "Default")
      (node (ref "R8") (pin "1") (pinfunction "1_1") (pintype "passive"))
      (node (ref "U$15") (pin "-") (pinfunction "-_-") (pintype "bidirectional"))
    )
    (net (code "58") (name "Net-(R26-Pad2)") (class "Default")
      (node (ref "R26") (pin "2") (pinfunction "2_2") (pintype "passive"))
      (node (ref "R27") (pin "1") (pinfunction "1_1") (pintype "passive"))
      (node (ref "S3") (pin "2") (pinfunction "2_2") (pintype "passive"))
    )
    (net (code "59") (name "Net-(U$5-Pad+)") (class "Default")
      (node (ref "U$5") (pin "+") (pinfunction "+_+") (pintype "bidirectional"))
      (node (ref "U$6") (pin "-") (pinfunction "-_-") (pintype "bidirectional"))
    )
    (net (code "60") (name "Net-(U$13-Pad-)") (class "Default")
      (node (ref "U$13") (pin "-") (pinfunction "-_-") (pintype "bidirectional"))
      (node (ref "U$14") (pin "+") (pinfunction "+_+") (pintype "bidirectional"))
    )
    (net (code "61") (name "Net-(U4-1C)") (class "Default")
      (node (ref "R5") (pin "2") (pinfunction "2_2") (pintype "passive"))
      (node (ref "U4") (pin "16") (pinfunction "1C_16") (pintype "output"))
    )
    (net (code "62") (name "Net-(U4-2C)") (class "Default")
      (node (ref "R6") (pin "2") (pinfunction "2_2") (pintype "passive"))
      (node (ref "U4") (pin "15") (pinfunction "2C_15") (pintype "output"))
    )
    (net (code "63") (name "Net-(U4-3C)") (class "Default")
      (node (ref "R7") (pin "2") (pinfunction "2_2") (pintype "passive"))
      (node (ref "U4") (pin "14") (pinfunction "3C_14") (pintype "output"))
    )
    (net (code "64") (name "Net-(U4-4C)") (class "Default")
      (node (ref "R8") (pin "2") (pinfunction "2_2") (pintype "passive"))
      (node (ref "U4") (pin "13") (pinfunction "4C_13") (pintype "output"))
    )
    (net (code "65") (name "unconnected-(STM32F405RGT6-PadPA2)") (class "Default")
      (node (ref "STM32F405RGT6") (pin "PA2") (pinfunction "PA2_PA2") (pintype "bidirectional"))
    )
    (net (code "66") (name "unconnected-(STM32F405RGT6-PadPA11)") (class "Default")
      (node (ref "STM32F405RGT6") (pin "PA11") (pinfunction "PA11_PA11") (pintype "bidirectional"))
    )
    (net (code "67") (name "unconnected-(STM32F405RGT6-PadPA12)") (class "Default")
      (node (ref "STM32F405RGT6") (pin "PA12") (pinfunction "PA12_PA12") (pintype "bidirectional"))
    )
    (net (code "68") (name "unconnected-(STM32F405RGT6-PadPB13)") (class "Default")
      (node (ref "STM32F405RGT6") (pin "PB13") (pinfunction "PB13_PB13") (pintype "bidirectional"))
    )
    (net (code "69") (name "unconnected-(STM32F405RGT6-PadPB14)") (class "Default")
      (node (ref "STM32F405RGT6") (pin "PB14") (pinfunction "PB14_PB14") (pintype "bidirectional"))
    )
    (net (code "70") (name "unconnected-(STM32F405RGT6-PadPB15)") (class "Default")
      (node (ref "STM32F405RGT6") (pin "PB15") (pinfunction "PB15_PB15") (pintype "bidirectional"))
    )
    (net (code "71") (name "unconnected-(STM32F405RGT6-PadPC0)") (class "Default")
      (node (ref "STM32F405RGT6") (pin "PC0") (pinfunction "PC0_PC0") (pintype "bidirectional"))
    )
    (net (code "72") (name "unconnected-(STM32F405RGT6-PadPC1)") (class "Default")
      (node (ref "STM32F405RGT6") (pin "PC1") (pinfunction "PC1_PC1") (pintype "bidirectional"))
    )
    (net (code "73") (name "unconnected-(STM32F405RGT6-PadPC6)") (class "Default")
      (node (ref "STM32F405RGT6") (pin "PC6") (pinfunction "PC6_PC6") (pintype "bidirectional"))
    )
    (net (code "74") (name "unconnected-(STM32F405RGT6-PadPC7)") (class "Default")
      (node (ref "STM32F405RGT6") (pin "PC7") (pinfunction "PC7_PC7") (pintype "bidirectional"))
    )
    (net (code "75") (name "unconnected-(STM32F405RGT6-PadPC8)") (class "Default")
      (node (ref "STM32F405RGT6") (pin "PC8") (pinfunction "PC8_PC8") (pintype "bidirectional"))
    )
    (net (code "76") (name "unconnected-(STM32F405RGT6-PadPC9)") (class "Default")
      (node (ref "STM32F405RGT6") (pin "PC9") (pinfunction "PC9_PC9") (pintype "bidirectional"))
    )
    (net (code "77") (name "unconnected-(STM32F405RGT6-PadPC10)") (class "Default")
      (node (ref "STM32F405RGT6") (pin "PC10") (pinfunction "PC10_PC10") (pintype "bidirectional"))
    )
    (net (code "78") (name "unconnected-(STM32F405RGT6-PadPC11)") (class "Default")
      (node (ref "STM32F405RGT6") (pin "PC11") (pinfunction "PC11_PC11") (pintype "bidirectional"))
    )
    (net (code "79") (name "unconnected-(STM32F405RGT6-PadPC12)") (class "Default")
      (node (ref "STM32F405RGT6") (pin "PC12") (pinfunction "PC12_PC12") (pintype "bidirectional"))
    )
    (net (code "80") (name "unconnected-(STM32F405RGT6-PadPC14)") (class "Default")
      (node (ref "STM32F405RGT6") (pin "PC14") (pinfunction "PC14_PC14") (pintype "bidirectional"))
    )
    (net (code "81") (name "unconnected-(STM32F405RGT6-PadPC15)") (class "Default")
      (node (ref "STM32F405RGT6") (pin "PC15") (pinfunction "PC15_PC15") (pintype "bidirectional"))
    )
    (net (code "82") (name "unconnected-(STM32F405RGT6-PadPD2)") (class "Default")
      (node (ref "STM32F405RGT6") (pin "PD2") (pinfunction "PD2_PD2") (pintype "bidirectional"))
    )
    (net (code "83") (name "unconnected-(STM32F405RGT6-PadPH0)") (class "Default")
      (node (ref "STM32F405RGT6") (pin "PH0") (pinfunction "PH0_PH0") (pintype "bidirectional"))
    )
    (net (code "84") (name "unconnected-(STM32F405RGT6-PadPH1)") (class "Default")
      (node (ref "STM32F405RGT6") (pin "PH1") (pinfunction "PH1_PH1") (pintype "bidirectional"))
    )
    (net (code "85") (name "unconnected-(U$2-PadM1)") (class "Default")
      (node (ref "U$2") (pin "M1") (pinfunction "M1_M1") (pintype "bidirectional"))
    )
    (net (code "86") (name "unconnected-(U$2-PadM2)") (class "Default")
      (node (ref "U$2") (pin "M2") (pinfunction "M2_M2") (pintype "bidirectional"))
    )
    (net (code "87") (name "unconnected-(U$3-PadM1)") (class "Default")
      (node (ref "U$3") (pin "M1") (pinfunction "M1_M1") (pintype "bidirectional"))
    )
    (net (code "88") (name "unconnected-(U$3-PadM2)") (class "Default")
      (node (ref "U$3") (pin "M2") (pinfunction "M2_M2") (pintype "bidirectional"))
    )
    (net (code "89") (name "unconnected-(U$8-PadPIN1)") (class "Default")
      (node (ref "U$8") (pin "PIN1") (pinfunction "PIN1_PIN1") (pintype "bidirectional"))
    )
    (net (code "90") (name "unconnected-(U$11-PadEEP)") (class "Default")
      (node (ref "U$11") (pin "EEP") (pinfunction "EEP_EEP") (pintype "bidirectional"))
    )
    (net (code "91") (name "unconnected-(U$11-PadULT)") (class "Default")
      (node (ref "U$11") (pin "ULT") (pinfunction "ULT_ULT") (pintype "bidirectional"))
    )
    (net (code "92") (name "unconnected-(U4-5C-Pad12)") (class "Default")
      (node (ref "U4") (pin "12") (pinfunction "5C_12") (pintype "output"))
    )
    (net (code "93") (name "unconnected-(U4-6B-Pad6)") (class "Default")
      (node (ref "U4") (pin "6") (pinfunction "6B_6") (pintype "input"))
    )
    (net (code "94") (name "unconnected-(U4-6C-Pad11)") (class "Default")
      (node (ref "U4") (pin "11") (pinfunction "6C_11") (pintype "output"))
    )
    (net (code "95") (name "unconnected-(U4-7B-Pad7)") (class "Default")
      (node (ref "U4") (pin "7") (pinfunction "7B_7") (pintype "input"))
    )
    (net (code "96") (name "unconnected-(U4-7C-Pad10)") (class "Default")
      (node (ref "U4") (pin "10") (pinfunction "7C_10") (pintype "output"))
    )
  )
)
